# DW1000.net
KiCad netlist of a schematic drawn in Altium Designer
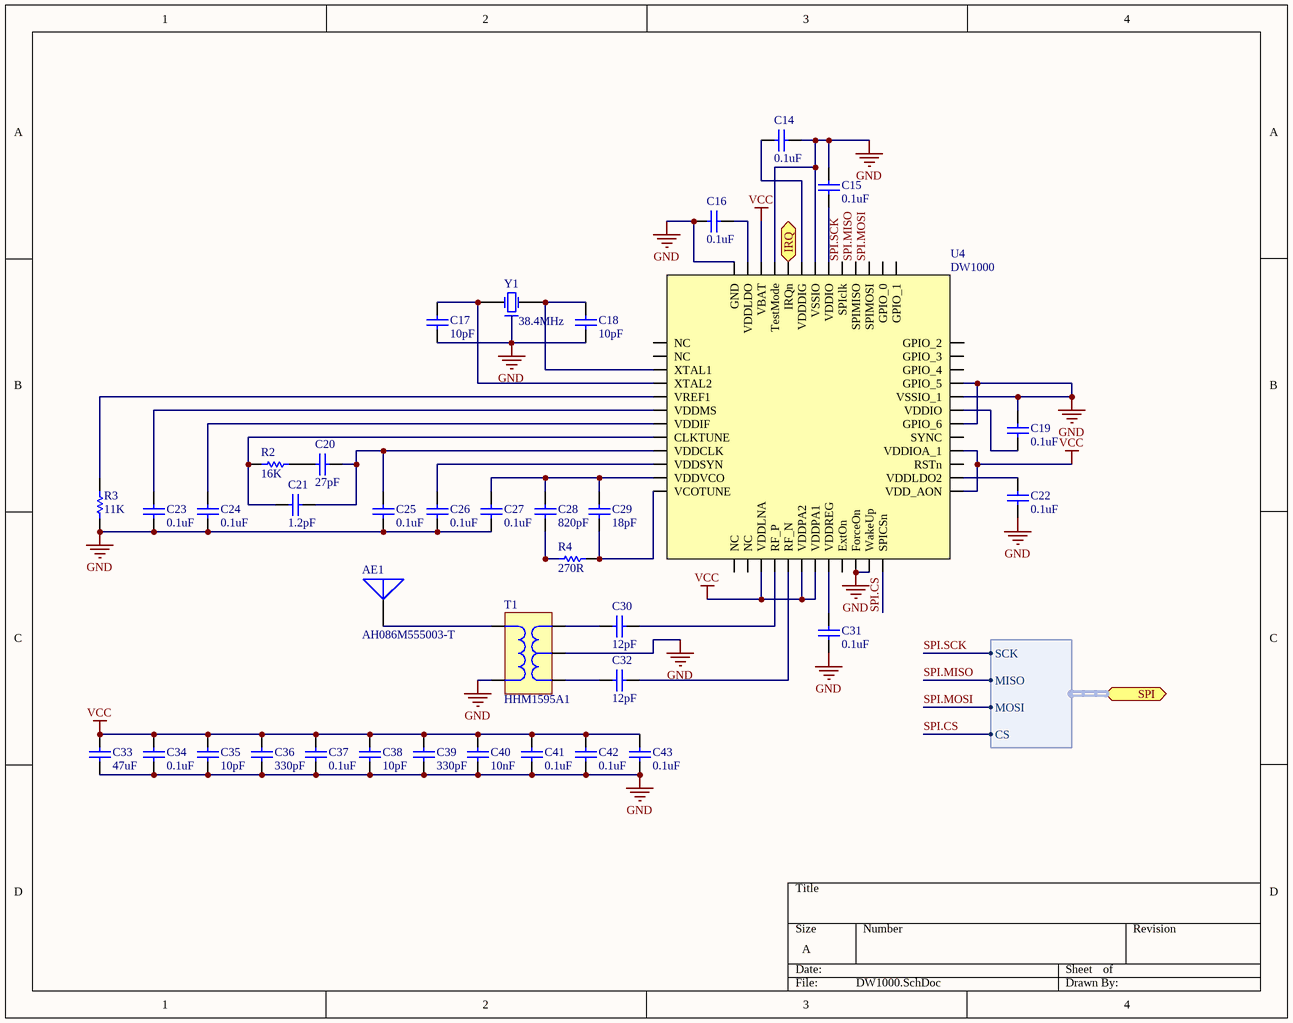
[diagram p0: DW1000.SchDoc]

(export (version "E")
  (design (tool "Eeschema 10.0.6"))
  (components
    (comp (ref "AE1")
      (value "AH086M555003-T")
      (footprint "AH086M555003-T")
      (fields (field (name "MANUFACTURER") "Taiyo Yuden"))
      (libsource (lib "Components") (part "AH086M555003-T"))
    )
    (comp (ref "C14")
      (value "0.1uF")
      (footprint "C0402[1005X55]")
      (description "0.1uF 6.3V 10% 0402 (1005 Metric)")
      (fields (field (name "PARTNUMBER") "GRM155R70J104KA01D") (field (name "MANUFACTURER") "Murata"))
      (libsource (lib "Capacitors") (part "CAP_0.1uF_6.3V_0402_10%"))
    )
    (comp (ref "C15")
      (value "0.1uF")
      (footprint "C0402[1005X55]")
      (description "0.1uF 6.3V 10% 0402 (1005 Metric)")
      (fields (field (name "PARTNUMBER") "GRM155R70J104KA01D") (field (name "MANUFACTURER") "Murata"))
      (libsource (lib "Capacitors") (part "CAP_0.1uF_6.3V_0402_10%"))
    )
    (comp (ref "C16")
      (value "0.1uF")
      (footprint "C0402[1005X55]")
      (description "0.1uF 6.3V 10% 0402 (1005 Metric)")
      (fields (field (name "PARTNUMBER") "GRM155R70J104KA01D") (field (name "MANUFACTURER") "Murata"))
      (libsource (lib "Capacitors") (part "CAP_0.1uF_6.3V_0402_10%"))
    )
    (comp (ref "C17")
      (value "10pF")
      (footprint "C0402[1005X55]")
      (description "10pF 50V 1% 0402 (1005 Metric)")
      (fields (field (name "PARTNUMBER") "GRM1555C1H100FA01D") (field (name "MANUFACTURER") "Murata"))
      (libsource (lib "Capacitors") (part "CAP_10pF_50V_0402_1%"))
    )
    (comp (ref "C18")
      (value "10pF")
      (footprint "C0402[1005X55]")
      (description "10pF 50V 1% 0402 (1005 Metric)")
      (fields (field (name "PARTNUMBER") "GRM1555C1H100FA01D") (field (name "MANUFACTURER") "Murata"))
      (libsource (lib "Capacitors") (part "CAP_10pF_50V_0402_1%"))
    )
    (comp (ref "C19")
      (value "0.1uF")
      (footprint "C0402[1005X55]")
      (description "0.1uF 6.3V 10% 0402 (1005 Metric)")
      (fields (field (name "PARTNUMBER") "GRM155R70J104KA01D") (field (name "MANUFACTURER") "Murata"))
      (libsource (lib "Capacitors") (part "CAP_0.1uF_6.3V_0402_10%"))
    )
    (comp (ref "C20")
      (value "27pF")
      (footprint "C0402[1005X55]")
      (description "27pF 50V 1% 0402 (1005 Metric)")
      (fields (field (name "PARTNUMBER") "GRM1555C1H270FA01D") (field (name "MANUFACTURER") "Murata"))
      (libsource (lib "Capacitors") (part "CAP_27pF_50V_0402_1%"))
    )
    (comp (ref "C21")
      (value "1.2pF")
      (footprint "C0402[1005X55]")
      (description "1.2pF 50V 0.05pF 0402 (1005 Metric)")
      (fields (field (name "PARTNUMBER") "GRM1555C1H1R2WA01D") (field (name "MANUFACTURER") "Murata"))
      (libsource (lib "Capacitors") (part "CAP_1.2pF_50V_0402_0.05pF"))
    )
    (comp (ref "C22")
      (value "0.1uF")
      (footprint "C0402[1005X55]")
      (description "0.1uF 6.3V 10% 0402 (1005 Metric)")
      (fields (field (name "PARTNUMBER") "GRM155R70J104KA01D") (field (name "MANUFACTURER") "Murata"))
      (libsource (lib "Capacitors") (part "CAP_0.1uF_6.3V_0402_10%"))
    )
    (comp (ref "C23")
      (value "0.1uF")
      (footprint "C0402[1005X55]")
      (description "0.1uF 6.3V 10% 0402 (1005 Metric)")
      (fields (field (name "PARTNUMBER") "GRM155R70J104KA01D") (field (name "MANUFACTURER") "Murata"))
      (libsource (lib "Capacitors") (part "CAP_0.1uF_6.3V_0402_10%"))
    )
    (comp (ref "C24")
      (value "0.1uF")
      (footprint "C0402[1005X55]")
      (description "0.1uF 6.3V 10% 0402 (1005 Metric)")
      (fields (field (name "PARTNUMBER") "GRM155R70J104KA01D") (field (name "MANUFACTURER") "Murata"))
      (libsource (lib "Capacitors") (part "CAP_0.1uF_6.3V_0402_10%"))
    )
    (comp (ref "C25")
      (value "0.1uF")
      (footprint "C0402[1005X55]")
      (description "0.1uF 6.3V 10% 0402 (1005 Metric)")
      (fields (field (name "PARTNUMBER") "GRM155R70J104KA01D") (field (name "MANUFACTURER") "Murata"))
      (libsource (lib "Capacitors") (part "CAP_0.1uF_6.3V_0402_10%"))
    )
    (comp (ref "C26")
      (value "0.1uF")
      (footprint "C0402[1005X55]")
      (description "0.1uF 6.3V 10% 0402 (1005 Metric)")
      (fields (field (name "PARTNUMBER") "GRM155R70J104KA01D") (field (name "MANUFACTURER") "Murata"))
      (libsource (lib "Capacitors") (part "CAP_0.1uF_6.3V_0402_10%"))
    )
    (comp (ref "C27")
      (value "0.1uF")
      (footprint "C0402[1005X55]")
      (description "0.1uF 6.3V 10% 0402 (1005 Metric)")
      (fields (field (name "PARTNUMBER") "GRM155R70J104KA01D") (field (name "MANUFACTURER") "Murata"))
      (libsource (lib "Capacitors") (part "CAP_0.1uF_6.3V_0402_10%"))
    )
    (comp (ref "C28")
      (value "820pF")
      (footprint "C0402[1005X55]")
      (description "820pF 50V 5% 0402 (1005 Metric)")
      (fields (field (name "PARTNUMBER") "GRM1555C1H821JA01D") (field (name "MANUFACTURER") "Murata"))
      (libsource (lib "Capacitors") (part "CAP_820pF_50V_0402_5%"))
    )
    (comp (ref "C29")
      (value "18pF")
      (footprint "C0402[1005X55]")
      (description "18pF 50V 1% 0402 (1005 Metric)")
      (fields (field (name "PARTNUMBER") "GRM1555C1H180FA01D") (field (name "MANUFACTURER") "Murata"))
      (libsource (lib "Capacitors") (part "CAP_18pF_50V_0402_1%"))
    )
    (comp (ref "C30")
      (value "12pF")
      (footprint "C0402[1005X55]")
      (description "12pF 50V 5% 0402 (1005 Metric)")
      (fields (field (name "PARTNUMBER") "GRM1555C1H120JA01D") (field (name "MANUFACTURER") "Murata"))
      (libsource (lib "Capacitors") (part "CAP_12pF_50V_0402_5%"))
    )
    (comp (ref "C31")
      (value "0.1uF")
      (footprint "C0402[1005X55]")
      (description "0.1uF 6.3V 10% 0402 (1005 Metric)")
      (fields (field (name "PARTNUMBER") "GRM155R70J104KA01D") (field (name "MANUFACTURER") "Murata"))
      (libsource (lib "Capacitors") (part "CAP_0.1uF_6.3V_0402_10%"))
    )
    (comp (ref "C32")
      (value "12pF")
      (footprint "C0402[1005X55]")
      (description "12pF 50V 5% 0402 (1005 Metric)")
      (fields (field (name "PARTNUMBER") "GRM1555C1H120JA01D") (field (name "MANUFACTURER") "Murata"))
      (libsource (lib "Capacitors") (part "CAP_12pF_50V_0402_5%"))
    )
    (comp (ref "C33")
      (value "47uF")
      (footprint "C1206[3216X160]")
      (description "47uF 6.3V 10% 1206 (3216 Metric)")
      (fields (field (name "PARTNUMBER") "GRM31CR60J476KE19L") (field (name "MANUFACTURER") "Murata"))
      (libsource (lib "Capacitors") (part "CAP_47uF_6.3V_1206_10%"))
    )
    (comp (ref "C34")
      (value "0.1uF")
      (footprint "C0402[1005X55]")
      (description "0.1uF 6.3V 10% 0402 (1005 Metric)")
      (fields (field (name "PARTNUMBER") "GRM155R70J104KA01D") (field (name "MANUFACTURER") "Murata"))
      (libsource (lib "Capacitors") (part "CAP_0.1uF_6.3V_0402_10%"))
    )
    (comp (ref "C35")
      (value "10pF")
      (footprint "C0402[1005X55]")
      (description "10pF 50V 1% 0402 (1005 Metric)")
      (fields (field (name "PARTNUMBER") "GRM1555C1H100FA01D") (field (name "MANUFACTURER") "Murata"))
      (libsource (lib "Capacitors") (part "CAP_10pF_50V_0402_1%"))
    )
    (comp (ref "C36")
      (value "330pF")
      (footprint "C0402[1005X55]")
      (description "330pF 50V 5% 0402 (1005 Metric)")
      (fields (field (name "PARTNUMBER") "GRM1555C1H331JA01D") (field (name "MANUFACTURER") "Murata"))
      (libsource (lib "Capacitors") (part "CAP_330pF_50V_0402_5%"))
    )
    (comp (ref "C37")
      (value "0.1uF")
      (footprint "C0402[1005X55]")
      (description "0.1uF 6.3V 10% 0402 (1005 Metric)")
      (fields (field (name "PARTNUMBER") "GRM155R70J104KA01D") (field (name "MANUFACTURER") "Murata"))
      (libsource (lib "Capacitors") (part "CAP_0.1uF_6.3V_0402_10%"))
    )
    (comp (ref "C38")
      (value "10pF")
      (footprint "C0402[1005X55]")
      (description "10pF 50V 1% 0402 (1005 Metric)")
      (fields (field (name "PARTNUMBER") "GRM1555C1H100FA01D") (field (name "MANUFACTURER") "Murata"))
      (libsource (lib "Capacitors") (part "CAP_10pF_50V_0402_1%"))
    )
    (comp (ref "C39")
      (value "330pF")
      (footprint "C0402[1005X55]")
      (description "330pF 50V 5% 0402 (1005 Metric)")
      (fields (field (name "PARTNUMBER") "GRM1555C1H331JA01D") (field (name "MANUFACTURER") "Murata"))
      (libsource (lib "Capacitors") (part "CAP_330pF_50V_0402_5%"))
    )
    (comp (ref "C40")
      (value "10nF")
      (footprint "C0402[1005X55]")
      (description "10nF 50V 10% 0402 (1005 Metric)")
      (fields (field (name "PARTNUMBER") "GCM155R71H103KA55D") (field (name "MANUFACTURER") "Murata"))
      (libsource (lib "Capacitors") (part "CAP_10nF_50V_0402_10%"))
    )
    (comp (ref "C41")
      (value "0.1uF")
      (footprint "C0402[1005X55]")
      (description "0.1uF 6.3V 10% 0402 (1005 Metric)")
      (fields (field (name "PARTNUMBER") "GRM155R70J104KA01D") (field (name "MANUFACTURER") "Murata"))
      (libsource (lib "Capacitors") (part "CAP_0.1uF_6.3V_0402_10%"))
    )
    (comp (ref "C42")
      (value "0.1uF")
      (footprint "C0402[1005X55]")
      (description "0.1uF 6.3V 10% 0402 (1005 Metric)")
      (fields (field (name "PARTNUMBER") "GRM155R70J104KA01D") (field (name "MANUFACTURER") "Murata"))
      (libsource (lib "Capacitors") (part "CAP_0.1uF_6.3V_0402_10%"))
    )
    (comp (ref "C43")
      (value "0.1uF")
      (footprint "C0402[1005X55]")
      (description "0.1uF 6.3V 10% 0402 (1005 Metric)")
      (fields (field (name "PARTNUMBER") "GRM155R70J104KA01D") (field (name "MANUFACTURER") "Murata"))
      (libsource (lib "Capacitors") (part "CAP_0.1uF_6.3V_0402_10%"))
    )
    (comp (ref "R2")
      (value "16K")
      (footprint "R0402[1005]")
      (description "16K 0.063W 1% 0402 (1005 Metric)")
      (fields (field (name "MANUFACTURER") "KOA Speer") (field (name "PARTNUMBER") "RK73H1ETTP1602F"))
      (libsource (lib "Resistors") (part "RES_16K_0402_1%"))
    )
    (comp (ref "R3")
      (value "11K")
      (footprint "R0402[1005]")
      (description "11K 0.063W 1% 0402 (1005 Metric)")
      (fields (field (name "MANUFACTURER") "KOA Speer") (field (name "PARTNUMBER") "RK73H1ETTP1102F"))
      (libsource (lib "Resistors") (part "RES_11K_0402_1%"))
    )
    (comp (ref "R4")
      (value "270R")
      (footprint "R0402[1005]")
      (description "270R 0.063W 1% 0402 (1005 Metric)")
      (fields (field (name "MANUFACTURER") "KOA Speer") (field (name "PARTNUMBER") "RK73H1ETTP2700F"))
      (libsource (lib "Resistors") (part "RES_270R_0402_1%"))
    )
    (comp (ref "T1")
      (value "HHM1595A1")
      (footprint "HHM1595A1")
      (fields (field (name "MANUFACTURER") "TDK"))
      (libsource (lib "Components") (part "HHM1595A1"))
    )
    (comp (ref "U4")
      (value "DW1000")
      (footprint "QFN-48")
      (description "UWB DW1000")
      (fields (field (name "PART NUMBER") "DW1000-I-TR13") (field (name "MANUFACTURER") "Decawave Limited"))
      (libsource (lib "ICs") (part "DW1000"))
    )
    (comp (ref "Y1")
      (value "38.4MHz")
      (footprint "ABRA-ABM10")
      (fields (field (name "PARTNUMBER") "ABM10-165-38.400MHZ-T3") (field (name "MANUFACTURER") "ABRACON"))
      (libsource (lib "Components") (part "ABM10-165-38.400MHZ-T3"))
    )
  )
  (nets
    (net (code "2") (name "/IRQ") (class "Default")
      (node (ref "U4") (pin "45") (pinfunction "IRQn_45") (pintype "passive"))
    )
    (net (code "3") (name "/SPI.CS") (class "Default")
      (node (ref "U4") (pin "24") (pinfunction "SPICSn_24") (pintype "passive"))
    )
    (net (code "4") (name "/SPI.MISO") (class "Default")
      (node (ref "U4") (pin "40") (pinfunction "SPIMISO_40") (pintype "passive"))
    )
    (net (code "5") (name "/SPI.MOSI") (class "Default")
      (node (ref "U4") (pin "39") (pinfunction "SPIMOSI_39") (pintype "passive"))
    )
    (net (code "6") (name "/SPI.SCK") (class "Default")
      (node (ref "U4") (pin "41") (pinfunction "SPIclk_41") (pintype "passive"))
    )
    (net (code "8") (name "GND") (class "Default")
      (node (ref "C14") (pin "1") (pinfunction "1_1") (pintype "passive"))
      (node (ref "C15") (pin "2") (pinfunction "2_2") (pintype "passive"))
      (node (ref "C16") (pin "2") (pinfunction "2_2") (pintype "passive"))
      (node (ref "C17") (pin "1") (pinfunction "1_1") (pintype "passive"))
      (node (ref "C18") (pin "1") (pinfunction "1_1") (pintype "passive"))
      (node (ref "C19") (pin "2") (pinfunction "2_2") (pintype "passive"))
      (node (ref "C22") (pin "1") (pinfunction "1_1") (pintype "passive"))
      (node (ref "C23") (pin "1") (pinfunction "1_1") (pintype "passive"))
      (node (ref "C24") (pin "1") (pinfunction "1_1") (pintype "passive"))
      (node (ref "C25") (pin "1") (pinfunction "1_1") (pintype "passive"))
      (node (ref "C26") (pin "1") (pinfunction "1_1") (pintype "passive"))
      (node (ref "C27") (pin "1") (pinfunction "1_1") (pintype "passive"))
      (node (ref "C31") (pin "1") (pinfunction "1_1") (pintype "passive"))
      (node (ref "C33") (pin "1") (pinfunction "1_1") (pintype "passive"))
      (node (ref "C34") (pin "1") (pinfunction "1_1") (pintype "passive"))
      (node (ref "C35") (pin "1") (pinfunction "1_1") (pintype "passive"))
      (node (ref "C36") (pin "1") (pinfunction "1_1") (pintype "passive"))
      (node (ref "C37") (pin "1") (pinfunction "1_1") (pintype "passive"))
      (node (ref "C38") (pin "1") (pinfunction "1_1") (pintype "passive"))
      (node (ref "C39") (pin "1") (pinfunction "1_1") (pintype "passive"))
      (node (ref "C40") (pin "1") (pinfunction "1_1") (pintype "passive"))
      (node (ref "C41") (pin "1") (pinfunction "1_1") (pintype "passive"))
      (node (ref "C42") (pin "1") (pinfunction "1_1") (pintype "passive"))
      (node (ref "C43") (pin "1") (pinfunction "1_1") (pintype "passive"))
      (node (ref "R3") (pin "1") (pinfunction "1_1") (pintype "passive"))
      (node (ref "T1") (pin "2") (pinfunction "2_2") (pintype "passive"))
      (node (ref "T1") (pin "5") (pinfunction "5_5") (pintype "passive"))
      (node (ref "U4") (pin "22") (pinfunction "ForceOn_22") (pintype "passive"))
      (node (ref "U4") (pin "23") (pinfunction "WakeUp_23") (pintype "passive"))
      (node (ref "U4") (pin "30") (pinfunction "GPIO_6_30") (pintype "passive"))
      (node (ref "U4") (pin "32") (pinfunction "VSSIO_1_32") (pintype "passive"))
      (node (ref "U4") (pin "33") (pinfunction "GPIO_5_33") (pintype "passive"))
      (node (ref "U4") (pin "43") (pinfunction "VSSIO_43") (pintype "passive"))
      (node (ref "U4") (pin "46") (pinfunction "TestMode_46") (pintype "passive"))
      (node (ref "U4") (pin "49") (pinfunction "GND_49") (pintype "passive"))
      (node (ref "Y1") (pin "2") (pinfunction "2_2") (pintype "passive"))
    )
    (net (code "9") (name "Net-(AE1-Pad1)") (class "Default")
      (node (ref "AE1") (pin "1") (pinfunction "1_1") (pintype "passive"))
      (node (ref "T1") (pin "1") (pinfunction "1_1") (pintype "passive"))
    )
    (net (code "10") (name "Net-(C15-Pad1)") (class "Default")
      (node (ref "C15") (pin "1") (pinfunction "1_1") (pintype "passive"))
      (node (ref "U4") (pin "42") (pinfunction "VDDIO_42") (pintype "passive"))
    )
    (net (code "11") (name "Net-(C19-Pad1)") (class "Default")
      (node (ref "C19") (pin "1") (pinfunction "1_1") (pintype "passive"))
      (node (ref "U4") (pin "31") (pinfunction "VDDIO_31") (pintype "passive"))
    )
    (net (code "12") (name "Net-(C20-Pad2)") (class "Default")
      (node (ref "C20") (pin "2") (pinfunction "2_2") (pintype "passive"))
      (node (ref "R2") (pin "1") (pinfunction "1_1") (pintype "passive"))
    )
    (net (code "13") (name "Net-(C28-Pad1)") (class "Default")
      (node (ref "C28") (pin "1") (pinfunction "1_1") (pintype "passive"))
      (node (ref "R4") (pin "1") (pinfunction "1_1") (pintype "passive"))
    )
    (net (code "14") (name "Net-(C30-Pad1)") (class "Default")
      (node (ref "C30") (pin "1") (pinfunction "1_1") (pintype "passive"))
      (node (ref "T1") (pin "4") (pinfunction "4_4") (pintype "passive"))
    )
    (net (code "15") (name "Net-(C32-Pad1)") (class "Default")
      (node (ref "C32") (pin "1") (pinfunction "1_1") (pintype "passive"))
      (node (ref "T1") (pin "3") (pinfunction "3_3") (pintype "passive"))
    )
    (net (code "16") (name "Net-(U4-CLKTUNE)") (class "Default")
      (node (ref "C21") (pin "2") (pinfunction "2_2") (pintype "passive"))
      (node (ref "R2") (pin "2") (pinfunction "2_2") (pintype "passive"))
      (node (ref "U4") (pin "8") (pinfunction "CLKTUNE_8") (pintype "passive"))
    )
    (net (code "17") (name "Net-(U4-RF_N)") (class "Default")
      (node (ref "C32") (pin "2") (pinfunction "2_2") (pintype "passive"))
      (node (ref "U4") (pin "17") (pinfunction "RF_N_17") (pintype "passive"))
    )
    (net (code "18") (name "Net-(U4-RF_P)") (class "Default")
      (node (ref "C30") (pin "2") (pinfunction "2_2") (pintype "passive"))
      (node (ref "U4") (pin "16") (pinfunction "RF_P_16") (pintype "passive"))
    )
    (net (code "19") (name "Net-(U4-VCOTUNE)") (class "Default")
      (node (ref "C29") (pin "1") (pinfunction "1_1") (pintype "passive"))
      (node (ref "R4") (pin "2") (pinfunction "2_2") (pintype "passive"))
      (node (ref "U4") (pin "12") (pinfunction "VCOTUNE_12") (pintype "passive"))
    )
    (net (code "20") (name "Net-(U4-VDDCLK)") (class "Default")
      (node (ref "C20") (pin "1") (pinfunction "1_1") (pintype "passive"))
      (node (ref "C21") (pin "1") (pinfunction "1_1") (pintype "passive"))
      (node (ref "C25") (pin "2") (pinfunction "2_2") (pintype "passive"))
      (node (ref "U4") (pin "9") (pinfunction "VDDCLK_9") (pintype "passive"))
    )
    (net (code "21") (name "Net-(U4-VDDDIG)") (class "Default")
      (node (ref "C14") (pin "2") (pinfunction "2_2") (pintype "passive"))
      (node (ref "U4") (pin "44") (pinfunction "VDDDIG_44") (pintype "passive"))
    )
    (net (code "22") (name "Net-(U4-VDDIF)") (class "Default")
      (node (ref "C24") (pin "2") (pinfunction "2_2") (pintype "passive"))
      (node (ref "U4") (pin "7") (pinfunction "VDDIF_7") (pintype "passive"))
    )
    (net (code "23") (name "Net-(U4-VDDLDO)") (class "Default")
      (node (ref "C16") (pin "1") (pinfunction "1_1") (pintype "passive"))
      (node (ref "U4") (pin "48") (pinfunction "VDDLDO_48") (pintype "passive"))
    )
    (net (code "24") (name "Net-(U4-VDDLDO2)") (class "Default")
      (node (ref "C22") (pin "2") (pinfunction "2_2") (pintype "passive"))
      (node (ref "U4") (pin "26") (pinfunction "VDDLDO2_26") (pintype "passive"))
    )
    (net (code "25") (name "Net-(U4-VDDMS)") (class "Default")
      (node (ref "C23") (pin "2") (pinfunction "2_2") (pintype "passive"))
      (node (ref "U4") (pin "6") (pinfunction "VDDMS_6") (pintype "passive"))
    )
    (net (code "26") (name "Net-(U4-VDDREG)") (class "Default")
      (node (ref "C31") (pin "2") (pinfunction "2_2") (pintype "passive"))
      (node (ref "U4") (pin "20") (pinfunction "VDDREG_20") (pintype "passive"))
    )
    (net (code "27") (name "Net-(U4-VDDSYN)") (class "Default")
      (node (ref "C26") (pin "2") (pinfunction "2_2") (pintype "passive"))
      (node (ref "U4") (pin "10") (pinfunction "VDDSYN_10") (pintype "passive"))
    )
    (net (code "28") (name "Net-(U4-VDDVCO)") (class "Default")
      (node (ref "C27") (pin "2") (pinfunction "2_2") (pintype "passive"))
      (node (ref "C28") (pin "2") (pinfunction "2_2") (pintype "passive"))
      (node (ref "C29") (pin "2") (pinfunction "2_2") (pintype "passive"))
      (node (ref "U4") (pin "11") (pinfunction "VDDVCO_11") (pintype "passive"))
    )
    (net (code "29") (name "Net-(U4-VREF1)") (class "Default")
      (node (ref "R3") (pin "2") (pinfunction "2_2") (pintype "passive"))
      (node (ref "U4") (pin "5") (pinfunction "VREF1_5") (pintype "passive"))
    )
    (net (code "30") (name "Net-(U4-XTAL1)") (class "Default")
      (node (ref "C18") (pin "2") (pinfunction "2_2") (pintype "passive"))
      (node (ref "U4") (pin "3") (pinfunction "XTAL1_3") (pintype "passive"))
      (node (ref "Y1") (pin "3") (pinfunction "X2_3") (pintype "passive"))
    )
    (net (code "31") (name "Net-(U4-XTAL2)") (class "Default")
      (node (ref "C17") (pin "2") (pinfunction "2_2") (pintype "passive"))
      (node (ref "U4") (pin "4") (pinfunction "XTAL2_4") (pintype "passive"))
      (node (ref "Y1") (pin "1") (pinfunction "X1_1") (pintype "passive"))
    )
    (net (code "32") (name "VCC") (class "Default")
      (node (ref "C33") (pin "2") (pinfunction "2_2") (pintype "passive"))
      (node (ref "C34") (pin "2") (pinfunction "2_2") (pintype "passive"))
      (node (ref "C35") (pin "2") (pinfunction "2_2") (pintype "passive"))
      (node (ref "C36") (pin "2") (pinfunction "2_2") (pintype "passive"))
      (node (ref "C37") (pin "2") (pinfunction "2_2") (pintype "passive"))
      (node (ref "C38") (pin "2") (pinfunction "2_2") (pintype "passive"))
      (node (ref "C39") (pin "2") (pinfunction "2_2") (pintype "passive"))
      (node (ref "C40") (pin "2") (pinfunction "2_2") (pintype "passive"))
      (node (ref "C41") (pin "2") (pinfunction "2_2") (pintype "passive"))
      (node (ref "C42") (pin "2") (pinfunction "2_2") (pintype "passive"))
      (node (ref "C43") (pin "2") (pinfunction "2_2") (pintype "passive"))
      (node (ref "U4") (pin "15") (pinfunction "VDDLNA_15") (pintype "passive"))
      (node (ref "U4") (pin "18") (pinfunction "VDDPA2_18") (pintype "passive"))
      (node (ref "U4") (pin "19") (pinfunction "VDDPA1_19") (pintype "passive"))
      (node (ref "U4") (pin "25") (pinfunction "VDD_AON_25") (pintype "passive"))
      (node (ref "U4") (pin "28") (pinfunction "VDDIOA_1_28") (pintype "passive"))
      (node (ref "U4") (pin "47") (pinfunction "VBAT_47") (pintype "passive"))
    )
    (net (code "33") (name "unconnected-(U4-ExtOn-Pad21)") (class "Default")
      (node (ref "U4") (pin "21") (pinfunction "ExtOn_21") (pintype "passive"))
    )
    (net (code "34") (name "unconnected-(U4-GPIO_0-Pad38)") (class "Default")
      (node (ref "U4") (pin "38") (pinfunction "GPIO_0_38") (pintype "passive"))
    )
    (net (code "35") (name "unconnected-(U4-GPIO_1-Pad37)") (class "Default")
      (node (ref "U4") (pin "37") (pinfunction "GPIO_1_37") (pintype "passive"))
    )
    (net (code "36") (name "unconnected-(U4-GPIO_2-Pad36)") (class "Default")
      (node (ref "U4") (pin "36") (pinfunction "GPIO_2_36") (pintype "passive"))
    )
    (net (code "37") (name "unconnected-(U4-GPIO_3-Pad35)") (class "Default")
      (node (ref "U4") (pin "35") (pinfunction "GPIO_3_35") (pintype "passive"))
    )
    (net (code "38") (name "unconnected-(U4-GPIO_4-Pad34)") (class "Default")
      (node (ref "U4") (pin "34") (pinfunction "GPIO_4_34") (pintype "passive"))
    )
    (net (code "39") (name "unconnected-(U4-NC-Pad1)") (class "Default")
      (node (ref "U4") (pin "1") (pinfunction "NC_1") (pintype "passive"))
    )
    (net (code "40") (name "unconnected-(U4-NC-Pad2)") (class "Default")
      (node (ref "U4") (pin "2") (pinfunction "NC_2") (pintype "passive"))
    )
    (net (code "41") (name "unconnected-(U4-NC-Pad13)") (class "Default")
      (node (ref "U4") (pin "13") (pinfunction "NC_13") (pintype "passive"))
    )
    (net (code "42") (name "unconnected-(U4-NC-Pad14)") (class "Default")
      (node (ref "U4") (pin "14") (pinfunction "NC_14") (pintype "passive"))
    )
    (net (code "43") (name "unconnected-(U4-RSTn-Pad27)") (class "Default")
      (node (ref "U4") (pin "27") (pinfunction "RSTn_27") (pintype "passive"))
    )
    (net (code "44") (name "unconnected-(U4-SYNC-Pad29)") (class "Default")
      (node (ref "U4") (pin "29") (pinfunction "SYNC_29") (pintype "passive"))
    )
  )
)
